# ArduinoShield_v1.net
KiCad netlist of a schematic drawn in EAGLE
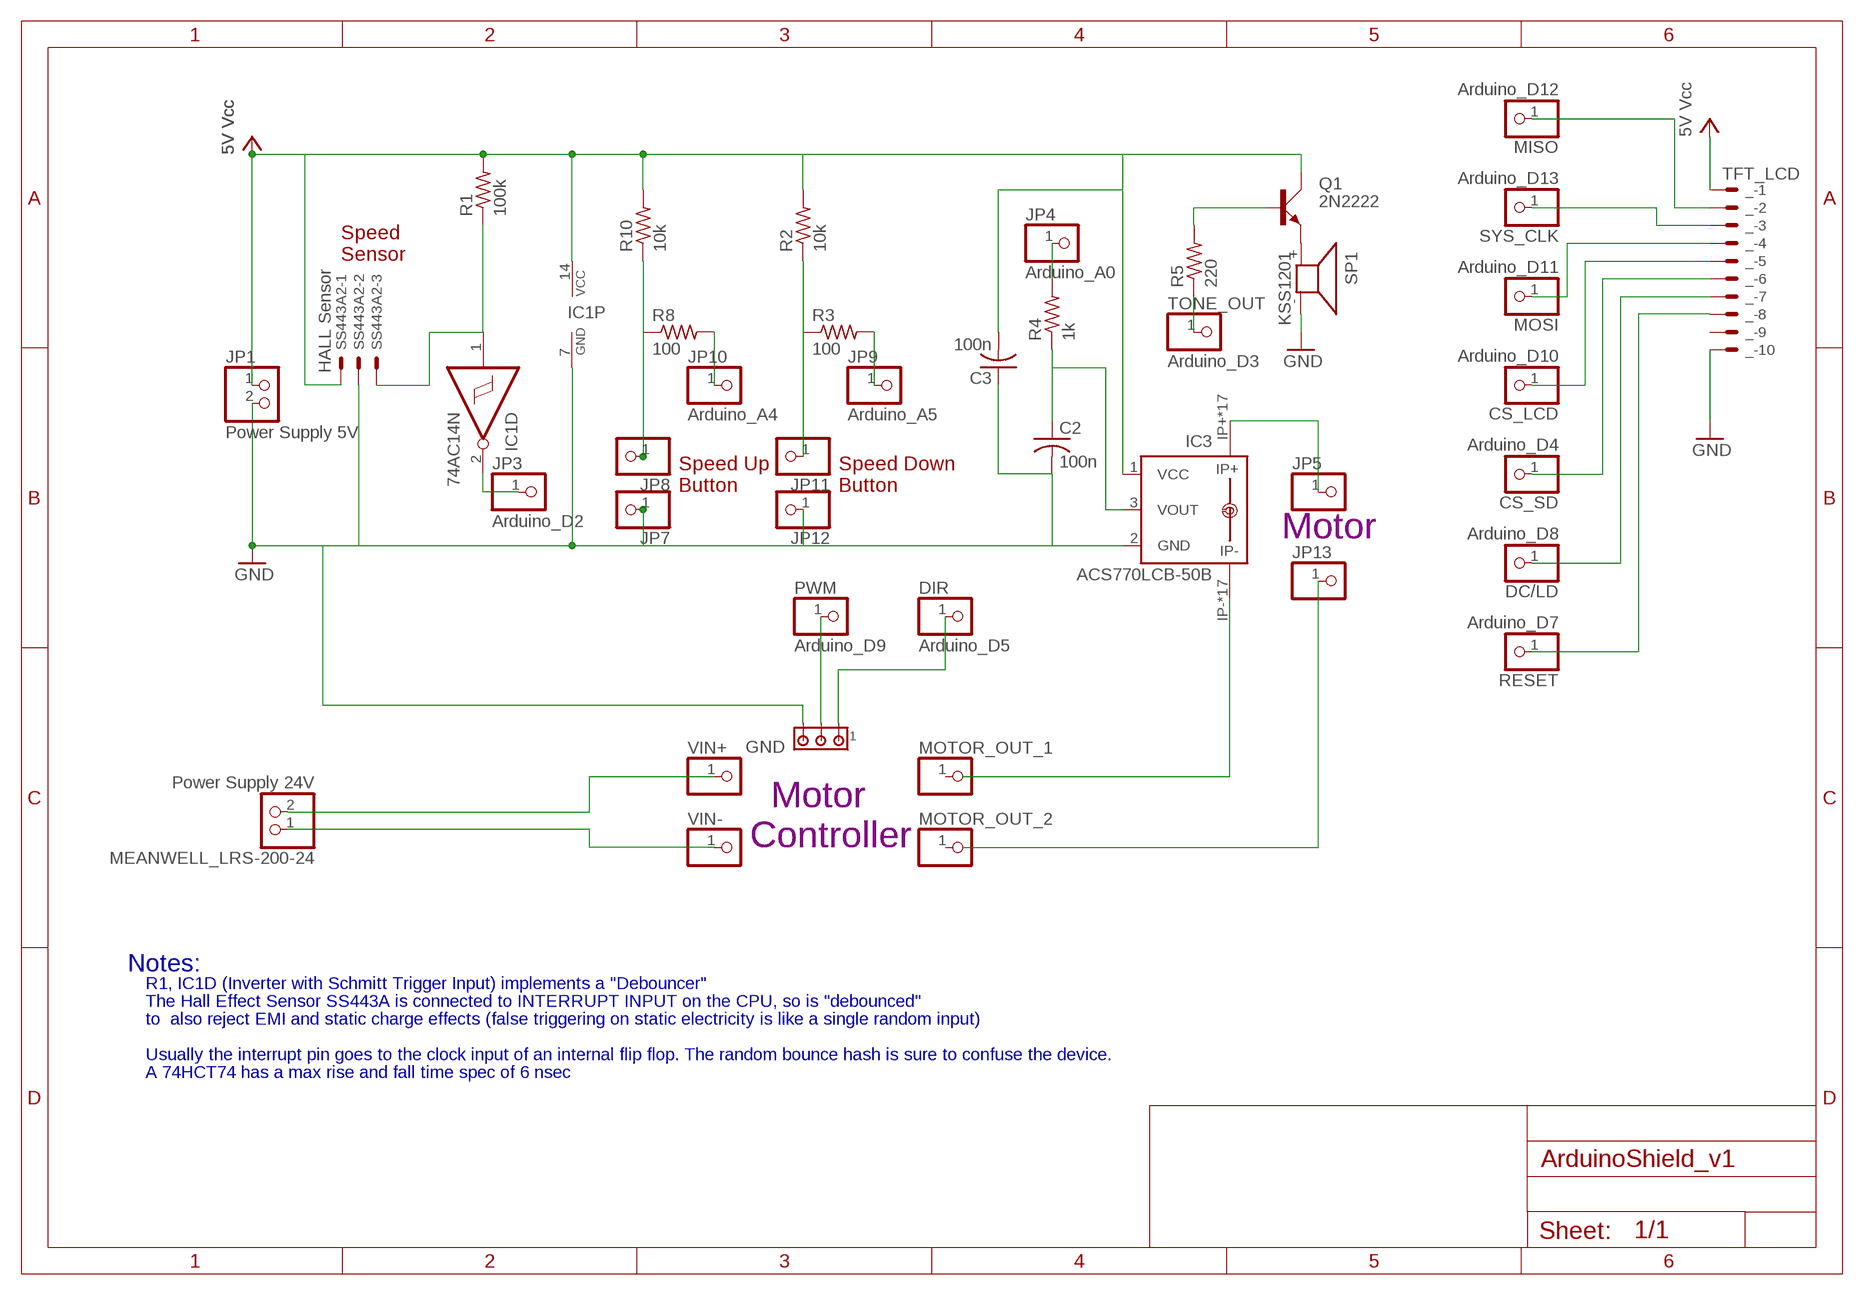
[diagram p0: schematic, sheet 1]

(export (version "E")
  (design (tool "Eeschema 10.0.6"))
  (components
    (comp (ref "C2")
      (value "100n")
      (footprint "eagle-import:C050-030X075")
      (libsource (lib "eagle-import") (part "C-US050-030X075"))
    )
    (comp (ref "C3")
      (value "100n")
      (footprint "eagle-import:C050-030X075")
      (libsource (lib "eagle-import") (part "C-US050-030X075"))
    )
    (comp (ref "CS_LCD")
      (value "Arduino_D10")
      (footprint "eagle-import:1X01")
      (libsource (lib "eagle-import") (part "PINHD-1X1"))
    )
    (comp (ref "CS_SD")
      (value "Arduino_D4")
      (footprint "eagle-import:1X01")
      (libsource (lib "eagle-import") (part "PINHD-1X1"))
    )
    (comp (ref "DC/LD")
      (value "Arduino_D8")
      (footprint "eagle-import:1X01")
      (libsource (lib "eagle-import") (part "PINHD-1X1"))
    )
    (comp (ref "DIR")
      (value "Arduino_D5")
      (footprint "eagle-import:1X01")
      (libsource (lib "eagle-import") (part "PINHD-1X1"))
    )
    (comp (ref "GND")
      (value "350429-1")
      (footprint "eagle-import:350429-1")
      (libsource (lib "eagle-import") (part "350429-1"))
    )
    (comp (ref "IC1")
      (value "74AC14N")
      (footprint "eagle-import:DIL14")
      (libsource (lib "eagle-import") (part "7414NAC"))
    )
    (comp (ref "IC3")
      (value "ACS770LCB-50B")
      (footprint "eagle-import:ACS75050")
      (fields (field (name "MF") "ALLEGRO MICROSYSTEMS, INC.") (field (name "MPN") "ACS750LCA-050"))
      (libsource (lib "eagle-import") (part "ACS750CA-050L"))
    )
    (comp (ref "JP1")
      (value "Power Supply 5V")
      (footprint "eagle-import:1X02")
      (libsource (lib "eagle-import") (part "PINHD-1X2"))
    )
    (comp (ref "JP3")
      (value "Arduino_D2")
      (footprint "eagle-import:1X01")
      (libsource (lib "eagle-import") (part "PINHD-1X1"))
    )
    (comp (ref "JP4")
      (value "Arduino_A0")
      (footprint "eagle-import:1X01")
      (libsource (lib "eagle-import") (part "PINHD-1X1"))
    )
    (comp (ref "JP5")
      (value "PINHD-1X1")
      (footprint "eagle-import:1X01")
      (libsource (lib "eagle-import") (part "PINHD-1X1"))
    )
    (comp (ref "JP7")
      (value "PINHD-1X1")
      (footprint "eagle-import:1X01")
      (libsource (lib "eagle-import") (part "PINHD-1X1"))
    )
    (comp (ref "JP8")
      (value "PINHD-1X1")
      (footprint "eagle-import:1X01")
      (libsource (lib "eagle-import") (part "PINHD-1X1"))
    )
    (comp (ref "JP9")
      (value "Arduino_A5")
      (footprint "eagle-import:1X01")
      (libsource (lib "eagle-import") (part "PINHD-1X1"))
    )
    (comp (ref "JP10")
      (value "Arduino_A4")
      (footprint "eagle-import:1X01")
      (libsource (lib "eagle-import") (part "PINHD-1X1"))
    )
    (comp (ref "JP11")
      (value "PINHD-1X1")
      (footprint "eagle-import:1X01")
      (libsource (lib "eagle-import") (part "PINHD-1X1"))
    )
    (comp (ref "JP12")
      (value "PINHD-1X1")
      (footprint "eagle-import:1X01")
      (libsource (lib "eagle-import") (part "PINHD-1X1"))
    )
    (comp (ref "JP13")
      (value "PINHD-1X1")
      (footprint "eagle-import:1X01")
      (libsource (lib "eagle-import") (part "PINHD-1X1"))
    )
    (comp (ref "MEANWELL_LRS-200-24")
      (value "Power Supply 24V")
      (footprint "eagle-import:1X02")
      (libsource (lib "eagle-import") (part "PINHD-1X2"))
    )
    (comp (ref "MISO")
      (value "Arduino_D12")
      (footprint "eagle-import:1X01")
      (libsource (lib "eagle-import") (part "PINHD-1X1"))
    )
    (comp (ref "MOSI")
      (value "Arduino_D11")
      (footprint "eagle-import:1X01")
      (libsource (lib "eagle-import") (part "PINHD-1X1"))
    )
    (comp (ref "MOTOR_OUT_1")
      (value "PINHD-1X1")
      (footprint "eagle-import:1X01")
      (libsource (lib "eagle-import") (part "PINHD-1X1"))
    )
    (comp (ref "MOTOR_OUT_2")
      (value "PINHD-1X1")
      (footprint "eagle-import:1X01")
      (libsource (lib "eagle-import") (part "PINHD-1X1"))
    )
    (comp (ref "PWM")
      (value "Arduino_D9")
      (footprint "eagle-import:1X01")
      (libsource (lib "eagle-import") (part "PINHD-1X1"))
    )
    (comp (ref "Q1")
      (value "2N2222")
      (footprint "eagle-import:TO18A")
      (libsource (lib "eagle-import") (part "2N2222"))
    )
    (comp (ref "R1")
      (value "100k")
      (footprint "eagle-import:0207_7")
      (libsource (lib "eagle-import") (part "R-US_0207/7"))
    )
    (comp (ref "R2")
      (value "10k")
      (footprint "eagle-import:0207_7")
      (libsource (lib "eagle-import") (part "R-US_0207/7"))
    )
    (comp (ref "R3")
      (value "100")
      (footprint "eagle-import:0207_7")
      (libsource (lib "eagle-import") (part "R-US_0207/7"))
    )
    (comp (ref "R4")
      (value "1k")
      (footprint "eagle-import:0207_7")
      (libsource (lib "eagle-import") (part "R-US_0207/7"))
    )
    (comp (ref "R5")
      (value "220")
      (footprint "eagle-import:0207_7")
      (libsource (lib "eagle-import") (part "R-US_0207/7"))
    )
    (comp (ref "R8")
      (value "100")
      (footprint "eagle-import:0207_7")
      (libsource (lib "eagle-import") (part "R-US_0207/7"))
    )
    (comp (ref "R10")
      (value "10k")
      (footprint "eagle-import:0207_7")
      (libsource (lib "eagle-import") (part "R-US_0207/7"))
    )
    (comp (ref "RESET")
      (value "Arduino_D7")
      (footprint "eagle-import:1X01")
      (libsource (lib "eagle-import") (part "PINHD-1X1"))
    )
    (comp (ref "SP1")
      (value "KSS1201")
      (footprint "eagle-import:KSS1201")
      (libsource (lib "eagle-import") (part "KSS1201"))
    )
    (comp (ref "SS443A2")
      (value "HALL Sensor")
      (footprint "eagle-import:22-23-2031")
      (fields (field (name "MF") "MOLEX") (field (name "MPN") "22-23-2031"))
      (libsource (lib "eagle-import") (part "22-23-2031"))
    )
    (comp (ref "SYS_CLK")
      (value "Arduino_D13")
      (footprint "eagle-import:1X01")
      (libsource (lib "eagle-import") (part "PINHD-1X1"))
    )
    (comp (ref "TONE_OUT")
      (value "Arduino_D3")
      (footprint "eagle-import:1X01")
      (libsource (lib "eagle-import") (part "PINHD-1X1"))
    )
    (comp (ref "VIN+")
      (value "PINHD-1X1")
      (footprint "eagle-import:1X01")
      (libsource (lib "eagle-import") (part "PINHD-1X1"))
    )
    (comp (ref "VIN-")
      (value "PINHD-1X1")
      (footprint "eagle-import:1X01")
      (libsource (lib "eagle-import") (part "PINHD-1X1"))
    )
    (comp (ref "_")
      (value "TFT_LCD")
      (footprint "eagle-import:22-23-2101")
      (fields (field (name "MF") "MOLEX") (field (name "MPN") "22-23-2101"))
      (libsource (lib "eagle-import") (part "22-23-2101"))
    )
  )
  (nets
    (net (code "1") (name "5V Vcc") (class "Default")
      (node (ref "C3") (pin "2") (pinfunction "2_2") (pintype "passive"))
      (node (ref "IC1") (pin "14") (pinfunction "VCC_14") (pintype "power_in"))
      (node (ref "IC3") (pin "1") (pinfunction "VCC_1") (pintype "power_in"))
      (node (ref "JP1") (pin "1") (pinfunction "1_1") (pintype "passive"))
      (node (ref "Q1") (pin "C") (pinfunction "C_C") (pintype "passive"))
      (node (ref "R1") (pin "2") (pinfunction "2_2") (pintype "passive"))
      (node (ref "R10") (pin "2") (pinfunction "2_2") (pintype "passive"))
      (node (ref "R2") (pin "2") (pinfunction "2_2") (pintype "passive"))
      (node (ref "SS443A2") (pin "1") (pinfunction "S_1") (pintype "passive"))
      (node (ref "_") (pin "1") (pinfunction "S_1") (pintype "passive"))
    )
    (net (code "2") (name "GND") (class "Default")
      (node (ref "C2") (pin "2") (pinfunction "2_2") (pintype "passive"))
      (node (ref "C3") (pin "1") (pinfunction "1_1") (pintype "passive"))
      (node (ref "GND") (pin "3") (pinfunction "3_3") (pintype "passive"))
      (node (ref "IC1") (pin "7") (pinfunction "GND_7") (pintype "power_in"))
      (node (ref "IC3") (pin "2") (pinfunction "GND_2") (pintype "power_in"))
      (node (ref "JP1") (pin "2") (pinfunction "2_2") (pintype "passive"))
      (node (ref "JP12") (pin "1") (pinfunction "1_1") (pintype "passive"))
      (node (ref "JP7") (pin "1") (pinfunction "1_1") (pintype "passive"))
      (node (ref "SP1") (pin "-") (pinfunction "2_-") (pintype "passive"))
      (node (ref "SS443A2") (pin "2") (pinfunction "S_2") (pintype "passive"))
      (node (ref "_") (pin "10") (pinfunction "S_10") (pintype "passive"))
    )
    (net (code "3") (name "Net-(DIR-Pad1)") (class "Default")
      (node (ref "DIR") (pin "1") (pinfunction "1_1") (pintype "passive"))
      (node (ref "GND") (pin "1") (pinfunction "1_1") (pintype "passive"))
    )
    (net (code "4") (name "Net-(GND-Pad2)") (class "Default")
      (node (ref "GND") (pin "2") (pinfunction "2_2") (pintype "passive"))
      (node (ref "PWM") (pin "1") (pinfunction "1_1") (pintype "passive"))
    )
    (net (code "5") (name "Net-(IC1D-I)") (class "Default")
      (node (ref "IC1") (pin "1") (pinfunction "I_1") (pintype "input"))
      (node (ref "R1") (pin "1") (pinfunction "1_1") (pintype "passive"))
      (node (ref "SS443A2") (pin "3") (pinfunction "S_3") (pintype "passive"))
    )
    (net (code "6") (name "Net-(IC1D-O)") (class "Default")
      (node (ref "IC1") (pin "2") (pinfunction "O_2") (pintype "output"))
      (node (ref "JP3") (pin "1") (pinfunction "1_1") (pintype "passive"))
    )
    (net (code "7") (name "Net-(IC3-IP+-PadIP+@10)") (class "Default")
      (node (ref "IC3") (pin "IP+") (pinfunction "IP+_IP+") (pintype "passive"))
      (node (ref "IC3") (pin "IP+@10") (pinfunction "IP+_IP+@10") (pintype "passive"))
      (node (ref "IC3") (pin "IP+@11") (pinfunction "IP+_IP+@11") (pintype "passive"))
      (node (ref "IC3") (pin "IP+@12") (pinfunction "IP+_IP+@12") (pintype "passive"))
      (node (ref "IC3") (pin "IP+@13") (pinfunction "IP+_IP+@13") (pintype "passive"))
      (node (ref "IC3") (pin "IP+@14") (pinfunction "IP+_IP+@14") (pintype "passive"))
      (node (ref "IC3") (pin "IP+@15") (pinfunction "IP+_IP+@15") (pintype "passive"))
      (node (ref "IC3") (pin "IP+@16") (pinfunction "IP+_IP+@16") (pintype "passive"))
      (node (ref "IC3") (pin "IP+@17") (pinfunction "IP+_IP+@17") (pintype "passive"))
      (node (ref "IC3") (pin "IP+@2") (pinfunction "IP+_IP+@2") (pintype "passive"))
      (node (ref "IC3") (pin "IP+@3") (pinfunction "IP+_IP+@3") (pintype "passive"))
      (node (ref "IC3") (pin "IP+@4") (pinfunction "IP+_IP+@4") (pintype "passive"))
      (node (ref "IC3") (pin "IP+@5") (pinfunction "IP+_IP+@5") (pintype "passive"))
      (node (ref "IC3") (pin "IP+@6") (pinfunction "IP+_IP+@6") (pintype "passive"))
      (node (ref "IC3") (pin "IP+@7") (pinfunction "IP+_IP+@7") (pintype "passive"))
      (node (ref "IC3") (pin "IP+@8") (pinfunction "IP+_IP+@8") (pintype "passive"))
      (node (ref "IC3") (pin "IP+@9") (pinfunction "IP+_IP+@9") (pintype "passive"))
      (node (ref "JP5") (pin "1") (pinfunction "1_1") (pintype "passive"))
    )
    (net (code "8") (name "Net-(IC3-IP--PadIP-@10)") (class "Default")
      (node (ref "IC3") (pin "IP-") (pinfunction "IP-_IP-") (pintype "passive"))
      (node (ref "IC3") (pin "IP-@10") (pinfunction "IP-_IP-@10") (pintype "passive"))
      (node (ref "IC3") (pin "IP-@11") (pinfunction "IP-_IP-@11") (pintype "passive"))
      (node (ref "IC3") (pin "IP-@12") (pinfunction "IP-_IP-@12") (pintype "passive"))
      (node (ref "IC3") (pin "IP-@13") (pinfunction "IP-_IP-@13") (pintype "passive"))
      (node (ref "IC3") (pin "IP-@14") (pinfunction "IP-_IP-@14") (pintype "passive"))
      (node (ref "IC3") (pin "IP-@15") (pinfunction "IP-_IP-@15") (pintype "passive"))
      (node (ref "IC3") (pin "IP-@16") (pinfunction "IP-_IP-@16") (pintype "passive"))
      (node (ref "IC3") (pin "IP-@17") (pinfunction "IP-_IP-@17") (pintype "passive"))
      (node (ref "IC3") (pin "IP-@2") (pinfunction "IP-_IP-@2") (pintype "passive"))
      (node (ref "IC3") (pin "IP-@3") (pinfunction "IP-_IP-@3") (pintype "passive"))
      (node (ref "IC3") (pin "IP-@4") (pinfunction "IP-_IP-@4") (pintype "passive"))
      (node (ref "IC3") (pin "IP-@5") (pinfunction "IP-_IP-@5") (pintype "passive"))
      (node (ref "IC3") (pin "IP-@6") (pinfunction "IP-_IP-@6") (pintype "passive"))
      (node (ref "IC3") (pin "IP-@7") (pinfunction "IP-_IP-@7") (pintype "passive"))
      (node (ref "IC3") (pin "IP-@8") (pinfunction "IP-_IP-@8") (pintype "passive"))
      (node (ref "IC3") (pin "IP-@9") (pinfunction "IP-_IP-@9") (pintype "passive"))
    )
    (net (code "9") (name "Net-(IC3-VOUT)") (class "Default")
      (node (ref "C2") (pin "1") (pinfunction "1_1") (pintype "passive"))
      (node (ref "IC3") (pin "3") (pinfunction "VOUT_3") (pintype "output"))
      (node (ref "R4") (pin "1") (pinfunction "1_1") (pintype "passive"))
    )
    (net (code "10") (name "Net-(JP4-Pad1)") (class "Default")
      (node (ref "JP4") (pin "1") (pinfunction "1_1") (pintype "passive"))
      (node (ref "R4") (pin "2") (pinfunction "2_2") (pintype "passive"))
    )
    (net (code "11") (name "Net-(JP8-Pad1)") (class "Default")
      (node (ref "JP8") (pin "1") (pinfunction "1_1") (pintype "passive"))
      (node (ref "R10") (pin "1") (pinfunction "1_1") (pintype "passive"))
      (node (ref "R8") (pin "1") (pinfunction "1_1") (pintype "passive"))
    )
    (net (code "12") (name "Net-(JP9-Pad1)") (class "Default")
      (node (ref "JP9") (pin "1") (pinfunction "1_1") (pintype "passive"))
      (node (ref "R3") (pin "2") (pinfunction "2_2") (pintype "passive"))
    )
    (net (code "13") (name "Net-(JP10-Pad1)") (class "Default")
      (node (ref "JP10") (pin "1") (pinfunction "1_1") (pintype "passive"))
      (node (ref "R8") (pin "2") (pinfunction "2_2") (pintype "passive"))
    )
    (net (code "14") (name "Net-(JP11-Pad1)") (class "Default")
      (node (ref "JP11") (pin "1") (pinfunction "1_1") (pintype "passive"))
      (node (ref "R2") (pin "1") (pinfunction "1_1") (pintype "passive"))
    )
    (net (code "15") (name "Net-(MEANWELL_LRS-200-24-Pad1)") (class "Default")
      (node (ref "MEANWELL_LRS-200-24") (pin "1") (pinfunction "1_1") (pintype "passive"))
      (node (ref "VIN-") (pin "1") (pinfunction "1_1") (pintype "passive"))
    )
    (net (code "16") (name "Net-(MEANWELL_LRS-200-24-Pad2)") (class "Default")
      (node (ref "MEANWELL_LRS-200-24") (pin "2") (pinfunction "2_2") (pintype "passive"))
      (node (ref "VIN+") (pin "1") (pinfunction "1_1") (pintype "passive"))
    )
    (net (code "17") (name "Net-(Q1-PadB)") (class "Default")
      (node (ref "Q1") (pin "B") (pinfunction "B_B") (pintype "passive"))
      (node (ref "R5") (pin "2") (pinfunction "2_2") (pintype "passive"))
    )
    (net (code "18") (name "Net-(R5-Pad1)") (class "Default")
      (node (ref "R5") (pin "1") (pinfunction "1_1") (pintype "passive"))
      (node (ref "TONE_OUT") (pin "1") (pinfunction "1_1") (pintype "passive"))
    )
    (net (code "19") (name "Net-(SP1-1)") (class "Default")
      (node (ref "Q1") (pin "E") (pinfunction "E_E") (pintype "passive"))
      (node (ref "SP1") (pin "+") (pinfunction "1_+") (pintype "passive"))
    )
    (net (code "20") (name "Net-(_C-S)") (class "Default")
      (node (ref "MISO") (pin "1") (pinfunction "1_1") (pintype "passive"))
      (node (ref "_") (pin "2") (pinfunction "S_2") (pintype "passive"))
    )
    (net (code "21") (name "Net-(_D-S)") (class "Default")
      (node (ref "SYS_CLK") (pin "1") (pinfunction "1_1") (pintype "passive"))
      (node (ref "_") (pin "3") (pinfunction "S_3") (pintype "passive"))
    )
    (net (code "22") (name "Net-(_E-S)") (class "Default")
      (node (ref "MOSI") (pin "1") (pinfunction "1_1") (pintype "passive"))
      (node (ref "_") (pin "4") (pinfunction "S_4") (pintype "passive"))
    )
    (net (code "23") (name "Net-(_F-S)") (class "Default")
      (node (ref "CS_LCD") (pin "1") (pinfunction "1_1") (pintype "passive"))
      (node (ref "_") (pin "5") (pinfunction "S_5") (pintype "passive"))
    )
    (net (code "24") (name "Net-(_G-S)") (class "Default")
      (node (ref "CS_SD") (pin "1") (pinfunction "1_1") (pintype "passive"))
      (node (ref "_") (pin "6") (pinfunction "S_6") (pintype "passive"))
    )
    (net (code "25") (name "Net-(_H-S)") (class "Default")
      (node (ref "DC/LD") (pin "1") (pinfunction "1_1") (pintype "passive"))
      (node (ref "_") (pin "7") (pinfunction "S_7") (pintype "passive"))
    )
    (net (code "26") (name "Net-(_I-S)") (class "Default")
      (node (ref "RESET") (pin "1") (pinfunction "1_1") (pintype "passive"))
      (node (ref "_") (pin "8") (pinfunction "S_8") (pintype "passive"))
    )
    (net (code "27") (name "unconnected-(JP13-Pad1)") (class "Default")
      (node (ref "JP13") (pin "1") (pinfunction "1_1") (pintype "passive"))
    )
    (net (code "28") (name "unconnected-(MOTOR_OUT_1-Pad1)") (class "Default")
      (node (ref "MOTOR_OUT_1") (pin "1") (pinfunction "1_1") (pintype "passive"))
    )
    (net (code "29") (name "unconnected-(MOTOR_OUT_2-Pad1)") (class "Default")
      (node (ref "MOTOR_OUT_2") (pin "1") (pinfunction "1_1") (pintype "passive"))
    )
    (net (code "30") (name "unconnected-(R3-Pad1)") (class "Default")
      (node (ref "R3") (pin "1") (pinfunction "1_1") (pintype "passive"))
    )
    (net (code "31") (name "unconnected-(_J-S-Pad9)") (class "Default")
      (node (ref "_") (pin "9") (pinfunction "S_9") (pintype "passive"))
    )
  )
)
